# Hank2.net
KiCad netlist of a schematic drawn in EAGLE
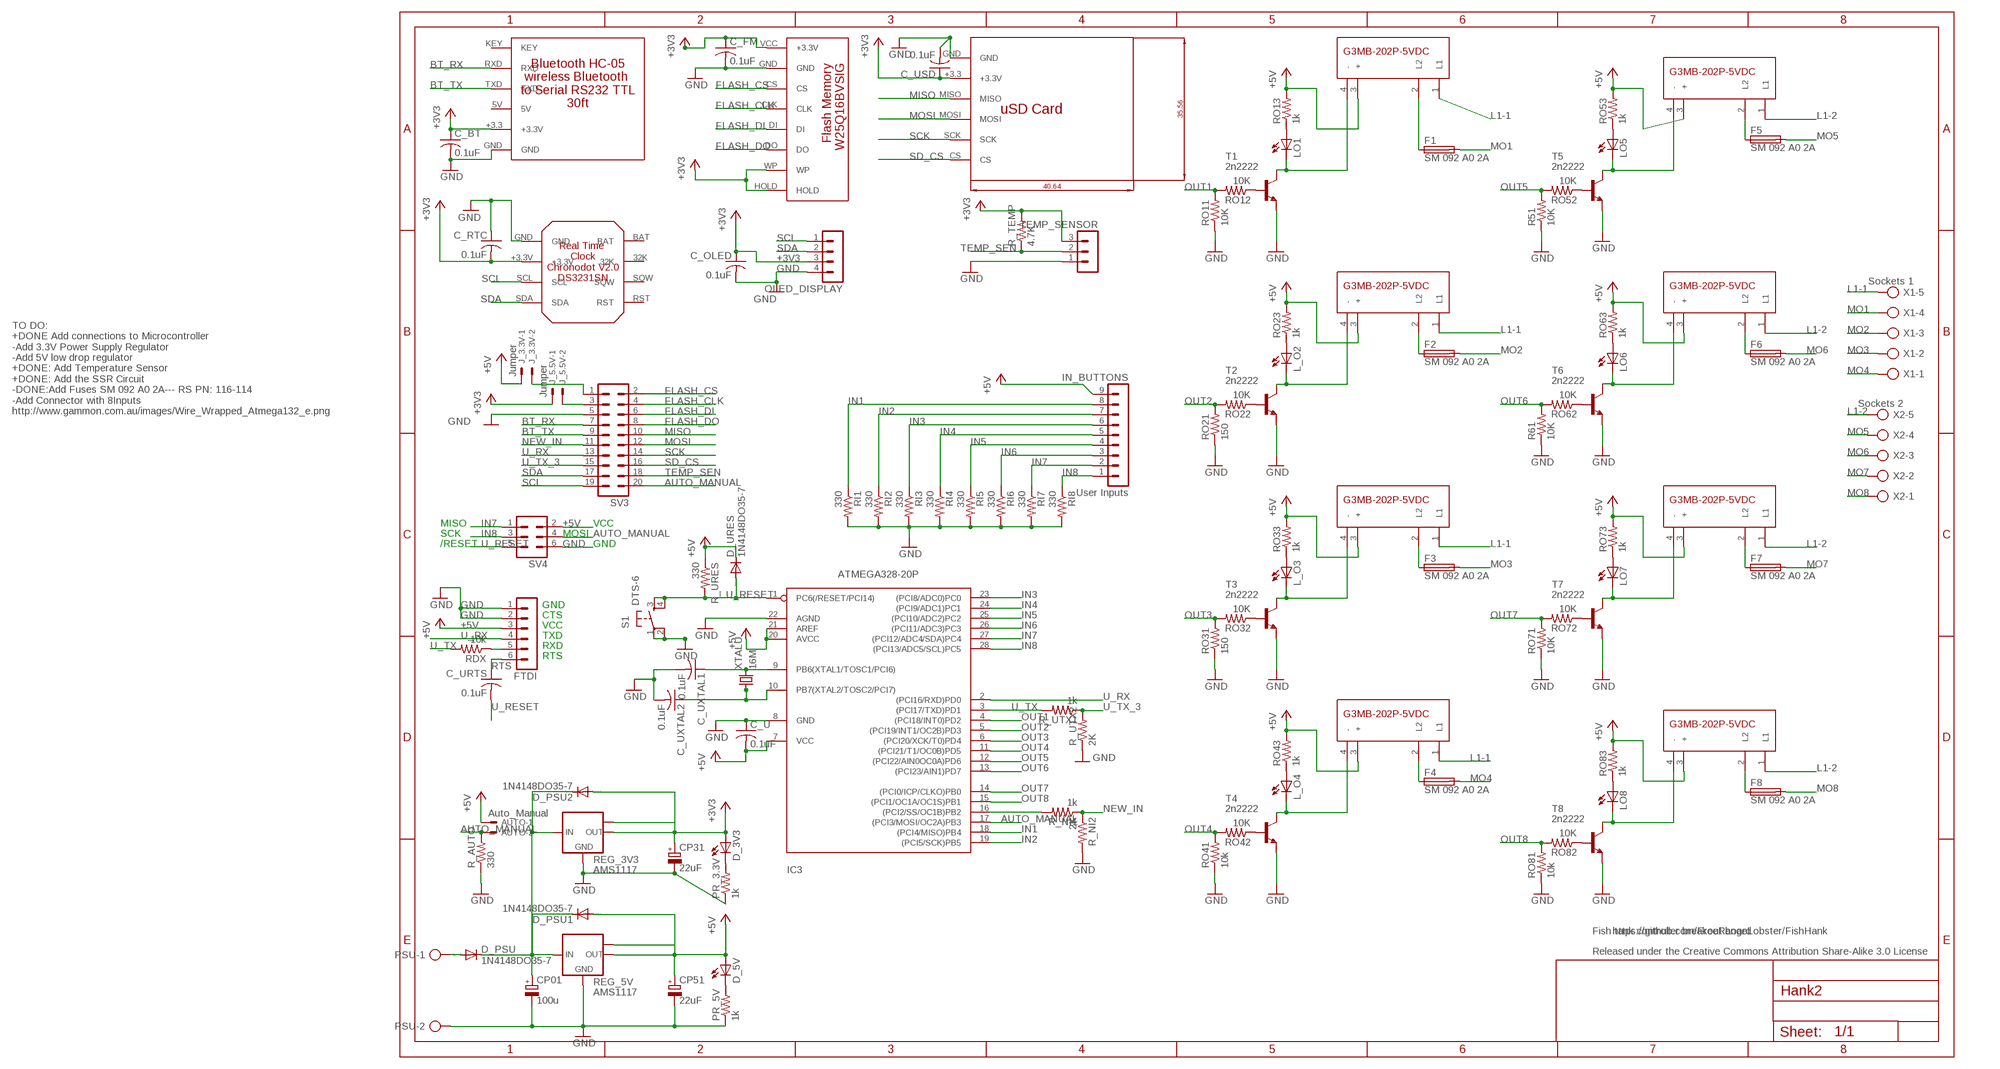
[diagram p0: schematic, sheet 1]

(export (version "E")
  (design (tool "Eeschema 10.0.6"))
  (components
    (comp (ref "AUTO")
      (value "Auto_Manual")
      (footprint "eagle-import:22-23-2021")
      (fields (field (name "MF") "MOLEX") (field (name "MPN") "22-23-2021"))
      (libsource (lib "eagle-import") (part "22-23-2021"))
    )
    (comp (ref "CP01")
      (value "100u")
      (footprint "eagle-import:E2,5-6")
      (libsource (lib "eagle-import") (part "CPOL-EUE2.5-6"))
    )
    (comp (ref "CP31")
      (value "22uF")
      (footprint "eagle-import:E2,5-6")
      (libsource (lib "eagle-import") (part "CPOL-EUE2.5-6"))
    )
    (comp (ref "CP51")
      (value "22uF")
      (footprint "eagle-import:E2,5-6")
      (libsource (lib "eagle-import") (part "CPOL-EUE2.5-6"))
    )
    (comp (ref "C_BT")
      (value "0.1uF")
      (footprint "eagle-import:C025-024X044")
      (libsource (lib "eagle-import") (part "C-US025-024X044"))
    )
    (comp (ref "C_FM")
      (value "0.1uF")
      (footprint "eagle-import:C025-024X044")
      (libsource (lib "eagle-import") (part "C-US025-024X044"))
    )
    (comp (ref "C_OLED")
      (value "0.1uF")
      (footprint "eagle-import:C025-024X044")
      (libsource (lib "eagle-import") (part "C-US025-024X044"))
    )
    (comp (ref "C_RTC")
      (value "0.1uF")
      (footprint "eagle-import:C025-024X044")
      (libsource (lib "eagle-import") (part "C-US025-024X044"))
    )
    (comp (ref "C_U")
      (value "0.1uF")
      (footprint "eagle-import:C025-024X044")
      (libsource (lib "eagle-import") (part "C-US025-024X044"))
    )
    (comp (ref "C_URTS")
      (value "0.1uF")
      (footprint "eagle-import:C025-024X044")
      (libsource (lib "eagle-import") (part "C-US025-024X044"))
    )
    (comp (ref "C_USD")
      (value "0.1uF")
      (footprint "eagle-import:C025-024X044")
      (libsource (lib "eagle-import") (part "C-US025-024X044"))
    )
    (comp (ref "C_UXTAL1")
      (value "0.1uF")
      (footprint "eagle-import:C025-024X044")
      (libsource (lib "eagle-import") (part "C-US025-024X044"))
    )
    (comp (ref "C_UXTAL2")
      (value "0.1uF")
      (footprint "eagle-import:C025-024X044")
      (libsource (lib "eagle-import") (part "C-US025-024X044"))
    )
    (comp (ref "D_3V3")
      (value "LED3MM")
      (footprint "eagle-import:LED3MM")
      (libsource (lib "eagle-import") (part "LED3MM"))
    )
    (comp (ref "D_5V")
      (value "LED3MM")
      (footprint "eagle-import:LED3MM")
      (libsource (lib "eagle-import") (part "LED3MM"))
    )
    (comp (ref "D_PSU")
      (value "1N4148DO35-7")
      (footprint "eagle-import:DO35-7")
      (libsource (lib "eagle-import") (part "1N4148DO35-7"))
    )
    (comp (ref "D_PSU1")
      (value "1N4148DO35-7")
      (footprint "eagle-import:DO35-7")
      (libsource (lib "eagle-import") (part "1N4148DO35-7"))
    )
    (comp (ref "D_PSU2")
      (value "1N4148DO35-7")
      (footprint "eagle-import:DO35-7")
      (libsource (lib "eagle-import") (part "1N4148DO35-7"))
    )
    (comp (ref "D_URES")
      (value "1N4148DO35-7")
      (footprint "eagle-import:DO35-7")
      (libsource (lib "eagle-import") (part "1N4148DO35-7"))
    )
    (comp (ref "F1")
      (value "SM 092 A0 2A")
      (footprint "eagle-import:PICOFUSE")
      (libsource (lib "eagle-import") (part "FUSEPICOFUSE"))
    )
    (comp (ref "F2")
      (value "SM 092 A0 2A")
      (footprint "eagle-import:PICOFUSE")
      (libsource (lib "eagle-import") (part "FUSEPICOFUSE"))
    )
    (comp (ref "F3")
      (value "SM 092 A0 2A")
      (footprint "eagle-import:PICOFUSE")
      (libsource (lib "eagle-import") (part "FUSEPICOFUSE"))
    )
    (comp (ref "F4")
      (value "SM 092 A0 2A")
      (footprint "eagle-import:PICOFUSE")
      (libsource (lib "eagle-import") (part "FUSEPICOFUSE"))
    )
    (comp (ref "F5")
      (value "SM 092 A0 2A")
      (footprint "eagle-import:PICOFUSE")
      (libsource (lib "eagle-import") (part "FUSEPICOFUSE"))
    )
    (comp (ref "F6")
      (value "SM 092 A0 2A")
      (footprint "eagle-import:PICOFUSE")
      (libsource (lib "eagle-import") (part "FUSEPICOFUSE"))
    )
    (comp (ref "F7")
      (value "SM 092 A0 2A")
      (footprint "eagle-import:PICOFUSE")
      (libsource (lib "eagle-import") (part "FUSEPICOFUSE"))
    )
    (comp (ref "F8")
      (value "SM 092 A0 2A")
      (footprint "eagle-import:PICOFUSE")
      (libsource (lib "eagle-import") (part "FUSEPICOFUSE"))
    )
    (comp (ref "FTDI")
      (value "MA06-1")
      (footprint "eagle-import:MA06-1")
      (libsource (lib "eagle-import") (part "MA06-1"))
    )
    (comp (ref "IC3")
      (value "ATMEGA328-20P")
      (footprint "eagle-import:DIL28-3")
      (libsource (lib "eagle-import") (part "ATMEGA328P-20"))
    )
    (comp (ref "IN_BUTTONS")
      (value "User Inputs")
      (footprint "eagle-import:MA09-1")
      (libsource (lib "eagle-import") (part "MA09-1"))
    )
    (comp (ref "J_3.3V")
      (value "Jumper")
      (footprint "eagle-import:22-23-2021")
      (fields (field (name "MF") "MOLEX") (field (name "MPN") "22-23-2021"))
      (libsource (lib "eagle-import") (part "22-23-2021"))
    )
    (comp (ref "J_5.5V")
      (value "Jumper")
      (footprint "eagle-import:22-23-2021")
      (fields (field (name "MF") "MOLEX") (field (name "MPN") "22-23-2021"))
      (libsource (lib "eagle-import") (part "22-23-2021"))
    )
    (comp (ref "LO1")
      (value "LED3MM")
      (footprint "eagle-import:LED3MM")
      (libsource (lib "eagle-import") (part "LED3MM"))
    )
    (comp (ref "LO5")
      (value "LED3MM")
      (footprint "eagle-import:LED3MM")
      (libsource (lib "eagle-import") (part "LED3MM"))
    )
    (comp (ref "LO6")
      (value "LED3MM")
      (footprint "eagle-import:LED3MM")
      (libsource (lib "eagle-import") (part "LED3MM"))
    )
    (comp (ref "LO7")
      (value "LED3MM")
      (footprint "eagle-import:LED3MM")
      (libsource (lib "eagle-import") (part "LED3MM"))
    )
    (comp (ref "LO8")
      (value "LED3MM")
      (footprint "eagle-import:LED3MM")
      (libsource (lib "eagle-import") (part "LED3MM"))
    )
    (comp (ref "L_O2")
      (value "LED3MM")
      (footprint "eagle-import:LED3MM")
      (libsource (lib "eagle-import") (part "LED3MM"))
    )
    (comp (ref "L_O3")
      (value "LED3MM")
      (footprint "eagle-import:LED3MM")
      (libsource (lib "eagle-import") (part "LED3MM"))
    )
    (comp (ref "L_O4")
      (value "LED3MM")
      (footprint "eagle-import:LED3MM")
      (libsource (lib "eagle-import") (part "LED3MM"))
    )
    (comp (ref "OLED_DISPLAY")
      (value "MA04-1")
      (footprint "eagle-import:MA04-1")
      (libsource (lib "eagle-import") (part "MA04-1"))
    )
    (comp (ref "PR_3.3V")
      (value "1k")
      (footprint "eagle-import:0207_10")
      (libsource (lib "eagle-import") (part "R-US_0207/10"))
    )
    (comp (ref "PR_5V")
      (value "1k")
      (footprint "eagle-import:0207_10")
      (libsource (lib "eagle-import") (part "R-US_0207/10"))
    )
    (comp (ref "PSU")
      (value "AK500/2")
      (footprint "eagle-import:AK500_2")
      (libsource (lib "eagle-import") (part "AK500/2"))
    )
    (comp (ref "R51")
      (value "10K")
      (footprint "eagle-import:0207_10")
      (libsource (lib "eagle-import") (part "R-US_0207/10"))
    )
    (comp (ref "R61")
      (value "10K")
      (footprint "eagle-import:0207_10")
      (libsource (lib "eagle-import") (part "R-US_0207/10"))
    )
    (comp (ref "RDX")
      (value "10k")
      (footprint "eagle-import:0207_10")
      (libsource (lib "eagle-import") (part "R-US_0207/10"))
    )
    (comp (ref "REG_3V3")
      (value "AMS1117")
      (footprint "eagle-import:SOT223")
      (libsource (lib "eagle-import") (part "AMS1117"))
    )
    (comp (ref "REG_5V")
      (value "AMS1117")
      (footprint "eagle-import:SOT223")
      (libsource (lib "eagle-import") (part "AMS1117"))
    )
    (comp (ref "RI1")
      (value "330")
      (footprint "eagle-import:0207_10")
      (libsource (lib "eagle-import") (part "R-US_0207/10"))
    )
    (comp (ref "RI2")
      (value "330")
      (footprint "eagle-import:0207_10")
      (libsource (lib "eagle-import") (part "R-US_0207/10"))
    )
    (comp (ref "RI3")
      (value "330")
      (footprint "eagle-import:0207_10")
      (libsource (lib "eagle-import") (part "R-US_0207/10"))
    )
    (comp (ref "RI4")
      (value "330")
      (footprint "eagle-import:0207_10")
      (libsource (lib "eagle-import") (part "R-US_0207/10"))
    )
    (comp (ref "RI5")
      (value "330")
      (footprint "eagle-import:0207_10")
      (libsource (lib "eagle-import") (part "R-US_0207/10"))
    )
    (comp (ref "RI6")
      (value "330")
      (footprint "eagle-import:0207_10")
      (libsource (lib "eagle-import") (part "R-US_0207/10"))
    )
    (comp (ref "RI7")
      (value "330")
      (footprint "eagle-import:0207_10")
      (libsource (lib "eagle-import") (part "R-US_0207/10"))
    )
    (comp (ref "RI8")
      (value "330")
      (footprint "eagle-import:0207_10")
      (libsource (lib "eagle-import") (part "R-US_0207/10"))
    )
    (comp (ref "RO11")
      (value "10K")
      (footprint "eagle-import:0207_10")
      (libsource (lib "eagle-import") (part "R-US_0207/10"))
    )
    (comp (ref "RO12")
      (value "10K")
      (footprint "eagle-import:0207_10")
      (libsource (lib "eagle-import") (part "R-US_0207/10"))
    )
    (comp (ref "RO13")
      (value "1k")
      (footprint "eagle-import:0207_10")
      (libsource (lib "eagle-import") (part "R-US_0207/10"))
    )
    (comp (ref "RO21")
      (value "150")
      (footprint "eagle-import:0207_10")
      (libsource (lib "eagle-import") (part "R-US_0207/10"))
    )
    (comp (ref "RO22")
      (value "10K")
      (footprint "eagle-import:0207_10")
      (libsource (lib "eagle-import") (part "R-US_0207/10"))
    )
    (comp (ref "RO23")
      (value "1k")
      (footprint "eagle-import:0207_10")
      (libsource (lib "eagle-import") (part "R-US_0207/10"))
    )
    (comp (ref "RO31")
      (value "150")
      (footprint "eagle-import:0207_10")
      (libsource (lib "eagle-import") (part "R-US_0207/10"))
    )
    (comp (ref "RO32")
      (value "10K")
      (footprint "eagle-import:0207_10")
      (libsource (lib "eagle-import") (part "R-US_0207/10"))
    )
    (comp (ref "RO33")
      (value "1k")
      (footprint "eagle-import:0207_10")
      (libsource (lib "eagle-import") (part "R-US_0207/10"))
    )
    (comp (ref "RO41")
      (value "10k")
      (footprint "eagle-import:0207_10")
      (libsource (lib "eagle-import") (part "R-US_0207/10"))
    )
    (comp (ref "RO42")
      (value "10K")
      (footprint "eagle-import:0207_10")
      (libsource (lib "eagle-import") (part "R-US_0207/10"))
    )
    (comp (ref "RO43")
      (value "1k")
      (footprint "eagle-import:0207_10")
      (libsource (lib "eagle-import") (part "R-US_0207/10"))
    )
    (comp (ref "RO52")
      (value "10K")
      (footprint "eagle-import:0207_10")
      (libsource (lib "eagle-import") (part "R-US_0207/10"))
    )
    (comp (ref "RO53")
      (value "1k")
      (footprint "eagle-import:0207_10")
      (libsource (lib "eagle-import") (part "R-US_0207/10"))
    )
    (comp (ref "RO62")
      (value "10K")
      (footprint "eagle-import:0207_10")
      (libsource (lib "eagle-import") (part "R-US_0207/10"))
    )
    (comp (ref "RO63")
      (value "1k")
      (footprint "eagle-import:0207_10")
      (libsource (lib "eagle-import") (part "R-US_0207/10"))
    )
    (comp (ref "RO71")
      (value "10K")
      (footprint "eagle-import:0207_10")
      (libsource (lib "eagle-import") (part "R-US_0207/10"))
    )
    (comp (ref "RO72")
      (value "10K")
      (footprint "eagle-import:0207_10")
      (libsource (lib "eagle-import") (part "R-US_0207/10"))
    )
    (comp (ref "RO73")
      (value "1k")
      (footprint "eagle-import:0207_10")
      (libsource (lib "eagle-import") (part "R-US_0207/10"))
    )
    (comp (ref "RO81")
      (value "10k")
      (footprint "eagle-import:0207_10")
      (libsource (lib "eagle-import") (part "R-US_0207/10"))
    )
    (comp (ref "RO82")
      (value "10K")
      (footprint "eagle-import:0207_10")
      (libsource (lib "eagle-import") (part "R-US_0207/10"))
    )
    (comp (ref "RO83")
      (value "1k")
      (footprint "eagle-import:0207_10")
      (libsource (lib "eagle-import") (part "R-US_0207/10"))
    )
    (comp (ref "R_AUTO")
      (value "330")
      (footprint "eagle-import:0207_10")
      (libsource (lib "eagle-import") (part "R-US_0207/10"))
    )
    (comp (ref "R_NI1")
      (value "1k")
      (footprint "eagle-import:0207_10")
      (libsource (lib "eagle-import") (part "R-US_0207/10"))
    )
    (comp (ref "R_NI2")
      (value "2K")
      (footprint "eagle-import:0207_10")
      (libsource (lib "eagle-import") (part "R-US_0207/10"))
    )
    (comp (ref "R_TEMP")
      (value "4.7K")
      (footprint "eagle-import:0207_10")
      (libsource (lib "eagle-import") (part "R-US_0207/10"))
    )
    (comp (ref "R_URES")
      (value "330")
      (footprint "eagle-import:0207_10")
      (libsource (lib "eagle-import") (part "R-US_0207/10"))
    )
    (comp (ref "R_UTX1")
      (value "1k")
      (footprint "eagle-import:0207_10")
      (libsource (lib "eagle-import") (part "R-US_0207/10"))
    )
    (comp (ref "R_UTX2")
      (value "2K")
      (footprint "eagle-import:0207_10")
      (libsource (lib "eagle-import") (part "R-US_0207/10"))
    )
    (comp (ref "S1")
      (value "DTS-6")
      (footprint "eagle-import:DTS-6")
      (libsource (lib "eagle-import") (part "DTS-6"))
    )
    (comp (ref "SSR1")
      (value "SSR")
      (footprint "eagle-import:SSR_FOOTPRINT")
      (libsource (lib "eagle-import") (part "SSR"))
    )
    (comp (ref "SSR2")
      (value "SSR")
      (footprint "eagle-import:SSR_FOOTPRINT")
      (libsource (lib "eagle-import") (part "SSR"))
    )
    (comp (ref "SSR3")
      (value "SSR")
      (footprint "eagle-import:SSR_FOOTPRINT")
      (libsource (lib "eagle-import") (part "SSR"))
    )
    (comp (ref "SSR4")
      (value "SSR")
      (footprint "eagle-import:SSR_FOOTPRINT")
      (libsource (lib "eagle-import") (part "SSR"))
    )
    (comp (ref "SSR5")
      (value "SSR")
      (footprint "eagle-import:SSR_FOOTPRINT")
      (libsource (lib "eagle-import") (part "SSR"))
    )
    (comp (ref "SSR6")
      (value "SSR")
      (footprint "eagle-import:SSR_FOOTPRINT")
      (libsource (lib "eagle-import") (part "SSR"))
    )
    (comp (ref "SSR7")
      (value "SSR")
      (footprint "eagle-import:SSR_FOOTPRINT")
      (libsource (lib "eagle-import") (part "SSR"))
    )
    (comp (ref "SSR8")
      (value "SSR")
      (footprint "eagle-import:SSR_FOOTPRINT")
      (libsource (lib "eagle-import") (part "SSR"))
    )
    (comp (ref "SV3")
      (value "MA10-2")
      (footprint "eagle-import:MA10-2")
      (libsource (lib "eagle-import") (part "MA10-2"))
    )
    (comp (ref "SV4")
      (value "MA03-2")
      (footprint "eagle-import:MA03-2")
      (libsource (lib "eagle-import") (part "MA03-2"))
    )
    (comp (ref "T1")
      (value "2n2222")
      (footprint "eagle-import:TO92-ECB")
      (libsource (lib "eagle-import") (part "2SC458"))
    )
    (comp (ref "T2")
      (value "2n2222")
      (footprint "eagle-import:TO92-ECB")
      (libsource (lib "eagle-import") (part "2SC458"))
    )
    (comp (ref "T3")
      (value "2n2222")
      (footprint "eagle-import:TO92-ECB")
      (libsource (lib "eagle-import") (part "2SC458"))
    )
    (comp (ref "T4")
      (value "2n2222")
      (footprint "eagle-import:TO92-ECB")
      (libsource (lib "eagle-import") (part "2SC458"))
    )
    (comp (ref "T5")
      (value "2n2222")
      (footprint "eagle-import:TO92-ECB")
      (libsource (lib "eagle-import") (part "2SC458"))
    )
    (comp (ref "T6")
      (value "2n2222")
      (footprint "eagle-import:TO92-ECB")
      (libsource (lib "eagle-import") (part "2SC458"))
    )
    (comp (ref "T7")
      (value "2n2222")
      (footprint "eagle-import:TO92-ECB")
      (libsource (lib "eagle-import") (part "2SC458"))
    )
    (comp (ref "T8")
      (value "2n2222")
      (footprint "eagle-import:TO92-ECB")
      (libsource (lib "eagle-import") (part "2SC458"))
    )
    (comp (ref "TEMP_SENSOR")
      (value "MA03-1")
      (footprint "eagle-import:MA03-1")
      (libsource (lib "eagle-import") (part "MA03-1"))
    )
    (comp (ref "U$1")
      (value "FLASH_MEMORY")
      (footprint "eagle-import:FLASHMEMORY_FOOTPRINT")
      (libsource (lib "eagle-import") (part "FLASH_MEMORY"))
    )
    (comp (ref "U$4")
      (value "BLUETOOTH")
      (footprint "eagle-import:BLUETOOTH_FOOTPRINT")
      (libsource (lib "eagle-import") (part "BLUETOOTH"))
    )
    (comp (ref "U$6")
      (value "RTC")
      (footprint "eagle-import:RTC_FOOTPRINT")
      (libsource (lib "eagle-import") (part "RTC"))
    )
    (comp (ref "U$7")
      (value "SD_CARD_READER")
      (footprint "eagle-import:SD_CARD_READER_FOOTPRINT")
      (libsource (lib "eagle-import") (part "SD_CARD_READER"))
    )
    (comp (ref "X1")
      (value "Sockets 1")
      (footprint "eagle-import:AK500_5")
      (libsource (lib "eagle-import") (part "AK500/5"))
    )
    (comp (ref "X2")
      (value "Sockets 2")
      (footprint "eagle-import:AK500_5")
      (libsource (lib "eagle-import") (part "AK500/5"))
    )
    (comp (ref "XTALU")
      (value "16M")
      (footprint "eagle-import:HC49_S")
      (libsource (lib "eagle-import") (part "CRYSTALHC49S"))
    )
  )
  (nets
    (net (code "1") (name "+3V3") (class "Default")
      (node (ref "CP31") (pin "+") (pinfunction "+_+") (pintype "passive"))
      (node (ref "C_BT") (pin "1") (pinfunction "1_1") (pintype "passive"))
      (node (ref "C_FM") (pin "1") (pinfunction "1_1") (pintype "passive"))
      (node (ref "C_OLED") (pin "1") (pinfunction "1_1") (pintype "passive"))
      (node (ref "C_RTC") (pin "2") (pinfunction "2_2") (pintype "passive"))
      (node (ref "C_USD") (pin "1") (pinfunction "1_1") (pintype "passive"))
      (node (ref "D_3V3") (pin "A") (pinfunction "A_A") (pintype "passive"))
      (node (ref "D_PSU2") (pin "A") (pinfunction "A_A") (pintype "passive"))
      (node (ref "J_5.5V") (pin "1") (pinfunction "S_1") (pintype "passive"))
      (node (ref "OLED_DISPLAY") (pin "3") (pinfunction "3_3") (pintype "passive"))
      (node (ref "REG_3V3") (pin "2") (pinfunction "OUT_2") (pintype "passive"))
      (node (ref "REG_3V3") (pin "TAB") (pinfunction "OUT1_TAB") (pintype "passive"))
      (node (ref "R_TEMP") (pin "2") (pinfunction "2_2") (pintype "passive"))
      (node (ref "TEMP_SENSOR") (pin "3") (pinfunction "3_3") (pintype "passive"))
      (node (ref "U$1") (pin "HOLD") (pinfunction "HOLD_HOLD") (pintype "bidirectional"))
      (node (ref "U$1") (pin "VCC") (pinfunction "+3.3V_VCC") (pintype "bidirectional"))
      (node (ref "U$1") (pin "WP") (pinfunction "WP_WP") (pintype "bidirectional"))
      (node (ref "U$4") (pin "+3.3") (pinfunction "+3.3V_+3.3") (pintype "bidirectional"))
      (node (ref "U$6") (pin "+3.3V") (pinfunction "+3.3V_+3.3V") (pintype "bidirectional"))
      (node (ref "U$7") (pin "+3.3") (pinfunction "+3.3V_+3.3") (pintype "bidirectional"))
    )
    (net (code "2") (name "+5V") (class "Default")
      (node (ref "AUTO") (pin "1") (pinfunction "S_1") (pintype "passive"))
      (node (ref "CP51") (pin "+") (pinfunction "+_+") (pintype "passive"))
      (node (ref "C_U") (pin "2") (pinfunction "2_2") (pintype "passive"))
      (node (ref "D_5V") (pin "A") (pinfunction "A_A") (pintype "passive"))
      (node (ref "D_PSU1") (pin "A") (pinfunction "A_A") (pintype "passive"))
      (node (ref "D_URES") (pin "C") (pinfunction "C_C") (pintype "passive"))
      (node (ref "FTDI") (pin "3") (pinfunction "3_3") (pintype "passive"))
      (node (ref "IC3") (pin "20") (pinfunction "AVCC_20") (pintype "bidirectional"))
      (node (ref "IC3") (pin "21") (pinfunction "AREF_21") (pintype "bidirectional"))
      (node (ref "IC3") (pin "7") (pinfunction "VCC_7") (pintype "bidirectional"))
      (node (ref "IN_BUTTONS") (pin "9") (pinfunction "9_9") (pintype "passive"))
      (node (ref "J_3.3V") (pin "1") (pinfunction "S_1") (pintype "passive"))
      (node (ref "REG_5V") (pin "2") (pinfunction "OUT_2") (pintype "passive"))
      (node (ref "REG_5V") (pin "TAB") (pinfunction "OUT1_TAB") (pintype "passive"))
      (node (ref "RO13") (pin "2") (pinfunction "2_2") (pintype "passive"))
      (node (ref "RO23") (pin "2") (pinfunction "2_2") (pintype "passive"))
      (node (ref "RO33") (pin "2") (pinfunction "2_2") (pintype "passive"))
      (node (ref "RO43") (pin "2") (pinfunction "2_2") (pintype "passive"))
      (node (ref "RO53") (pin "2") (pinfunction "2_2") (pintype "passive"))
      (node (ref "RO63") (pin "2") (pinfunction "2_2") (pintype "passive"))
      (node (ref "RO73") (pin "2") (pinfunction "2_2") (pintype "passive"))
      (node (ref "RO83") (pin "2") (pinfunction "2_2") (pintype "passive"))
      (node (ref "R_URES") (pin "1") (pinfunction "1_1") (pintype "passive"))
      (node (ref "SSR1") (pin "3") (pinfunction "+_3") (pintype "bidirectional"))
      (node (ref "SSR2") (pin "3") (pinfunction "+_3") (pintype "bidirectional"))
      (node (ref "SSR3") (pin "3") (pinfunction "+_3") (pintype "bidirectional"))
      (node (ref "SSR4") (pin "3") (pinfunction "+_3") (pintype "bidirectional"))
      (node (ref "SSR5") (pin "3") (pinfunction "+_3") (pintype "bidirectional"))
      (node (ref "SSR6") (pin "3") (pinfunction "+_3") (pintype "bidirectional"))
      (node (ref "SSR7") (pin "3") (pinfunction "+_3") (pintype "bidirectional"))
      (node (ref "SSR8") (pin "3") (pinfunction "+_3") (pintype "bidirectional"))
      (node (ref "SV4") (pin "2") (pinfunction "2_2") (pintype "passive"))
    )
    (net (code "3") (name "/AUTO_MANUAL") (class "Default")
      (node (ref "AUTO") (pin "2") (pinfunction "S_2") (pintype "passive"))
      (node (ref "IC3") (pin "17") (pinfunction "(PCI3/MOSI/OC2A)PB3_17") (pintype "bidirectional"))
      (node (ref "R_AUTO") (pin "2") (pinfunction "2_2") (pintype "passive"))
      (node (ref "SV3") (pin "20") (pinfunction "20_20") (pintype "passive"))
      (node (ref "SV4") (pin "4") (pinfunction "4_4") (pintype "passive"))
    )
    (net (code "4") (name "/BT_RX") (class "Default")
      (node (ref "SV3") (pin "7") (pinfunction "7_7") (pintype "passive"))
      (node (ref "U$4") (pin "RXD") (pinfunction "RXD_RXD") (pintype "bidirectional"))
    )
    (net (code "5") (name "/BT_TX") (class "Default")
      (node (ref "SV3") (pin "9") (pinfunction "9_9") (pintype "passive"))
      (node (ref "U$4") (pin "TXD") (pinfunction "TXD_TXD") (pintype "bidirectional"))
    )
    (net (code "6") (name "/FLASH_CLK") (class "Default")
      (node (ref "SV3") (pin "4") (pinfunction "4_4") (pintype "passive"))
      (node (ref "U$1") (pin "CLK") (pinfunction "CLK_CLK") (pintype "bidirectional"))
    )
    (net (code "7") (name "/FLASH_CS") (class "Default")
      (node (ref "SV3") (pin "2") (pinfunction "2_2") (pintype "passive"))
      (node (ref "U$1") (pin "CS") (pinfunction "CS_CS") (pintype "bidirectional"))
    )
    (net (code "8") (name "/FLASH_DI") (class "Default")
      (node (ref "SV3") (pin "6") (pinfunction "6_6") (pintype "passive"))
      (node (ref "U$1") (pin "DI") (pinfunction "DI_DI") (pintype "bidirectional"))
    )
    (net (code "9") (name "/FLASH_DO") (class "Default")
      (node (ref "SV3") (pin "8") (pinfunction "8_8") (pintype "passive"))
      (node (ref "U$1") (pin "DO") (pinfunction "DO_DO") (pintype "bidirectional"))
    )
    (net (code "10") (name "/IN1") (class "Default")
      (node (ref "IC3") (pin "18") (pinfunction "(PCI4/MISO)PB4_18") (pintype "bidirectional"))
      (node (ref "IN_BUTTONS") (pin "8") (pinfunction "8_8") (pintype "passive"))
      (node (ref "RI1") (pin "1") (pinfunction "1_1") (pintype "passive"))
    )
    (net (code "11") (name "/IN2") (class "Default")
      (node (ref "IC3") (pin "19") (pinfunction "(PCI5/SCK)PB5_19") (pintype "bidirectional"))
      (node (ref "IN_BUTTONS") (pin "7") (pinfunction "7_7") (pintype "passive"))
      (node (ref "RI2") (pin "1") (pinfunction "1_1") (pintype "passive"))
    )
    (net (code "12") (name "/IN3") (class "Default")
      (node (ref "IC3") (pin "23") (pinfunction "(PCI8/ADC0)PC0_23") (pintype "bidirectional"))
      (node (ref "IN_BUTTONS") (pin "6") (pinfunction "6_6") (pintype "passive"))
      (node (ref "RI3") (pin "1") (pinfunction "1_1") (pintype "passive"))
    )
    (net (code "13") (name "/IN4") (class "Default")
      (node (ref "IC3") (pin "24") (pinfunction "(PCI9/ADC1)PC1_24") (pintype "bidirectional"))
      (node (ref "IN_BUTTONS") (pin "5") (pinfunction "5_5") (pintype "passive"))
      (node (ref "RI4") (pin "1") (pinfunction "1_1") (pintype "passive"))
    )
    (net (code "14") (name "/IN5") (class "Default")
      (node (ref "IC3") (pin "25") (pinfunction "(PCI10/ADC2)PC2_25") (pintype "bidirectional"))
      (node (ref "IN_BUTTONS") (pin "4") (pinfunction "4_4") (pintype "passive"))
      (node (ref "RI5") (pin "1") (pinfunction "1_1") (pintype "passive"))
    )
    (net (code "15") (name "/IN6") (class "Default")
      (node (ref "IC3") (pin "26") (pinfunction "(PCI11/ADC3)PC3_26") (pintype "bidirectional"))
      (node (ref "IN_BUTTONS") (pin "3") (pinfunction "3_3") (pintype "passive"))
      (node (ref "RI6") (pin "1") (pinfunction "1_1") (pintype "passive"))
    )
    (net (code "16") (name "/IN7") (class "Default")
      (node (ref "IC3") (pin "27") (pinfunction "(PCI12/ADC4/SDA)PC4_27") (pintype "bidirectional"))
      (node (ref "IN_BUTTONS") (pin "2") (pinfunction "2_2") (pintype "passive"))
      (node (ref "RI7") (pin "1") (pinfunction "1_1") (pintype "passive"))
      (node (ref "SV4") (pin "1") (pinfunction "1_1") (pintype "passive"))
    )
    (net (code "17") (name "/IN8") (class "Default")
      (node (ref "IC3") (pin "28") (pinfunction "(PCI13/ADC5/SCL)PC5_28") (pintype "bidirectional"))
      (node (ref "IN_BUTTONS") (pin "1") (pinfunction "1_1") (pintype "passive"))
      (node (ref "RI8") (pin "1") (pinfunction "1_1") (pintype "passive"))
      (node (ref "SV4") (pin "3") (pinfunction "3_3") (pintype "passive"))
    )
    (net (code "18") (name "/L1-1") (class "Default")
      (node (ref "SSR1") (pin "1") (pinfunction "L1_1") (pintype "bidirectional"))
      (node (ref "SSR2") (pin "1") (pinfunction "L1_1") (pintype "bidirectional"))
      (node (ref "SSR3") (pin "1") (pinfunction "L1_1") (pintype "bidirectional"))
      (node (ref "SSR4") (pin "1") (pinfunction "L1_1") (pintype "bidirectional"))
      (node (ref "X1") (pin "5") (pinfunction "KL_5") (pintype "passive"))
    )
    (net (code "19") (name "/L1-2") (class "Default")
      (node (ref "SSR5") (pin "1") (pinfunction "L1_1") (pintype "bidirectional"))
      (node (ref "SSR6") (pin "1") (pinfunction "L1_1") (pintype "bidirectional"))
      (node (ref "SSR7") (pin "1") (pinfunction "L1_1") (pintype "bidirectional"))
      (node (ref "SSR8") (pin "1") (pinfunction "L1_1") (pintype "bidirectional"))
      (node (ref "X2") (pin "5") (pinfunction "KL_5") (pintype "passive"))
    )
    (net (code "20") (name "/MISO") (class "Default")
      (node (ref "SV3") (pin "10") (pinfunction "10_10") (pintype "passive"))
      (node (ref "U$7") (pin "MISO") (pinfunction "MISO_MISO") (pintype "bidirectional"))
    )
    (net (code "21") (name "/MO1") (class "Default")
      (node (ref "F1") (pin "2") (pinfunction "2_2") (pintype "passive"))
      (node (ref "X1") (pin "4") (pinfunction "KL_4") (pintype "passive"))
    )
    (net (code "22") (name "/MO2") (class "Default")
      (node (ref "F2") (pin "2") (pinfunction "2_2") (pintype "passive"))
      (node (ref "X1") (pin "3") (pinfunction "KL_3") (pintype "passive"))
    )
    (net (code "23") (name "/MO3") (class "Default")
      (node (ref "F3") (pin "2") (pinfunction "2_2") (pintype "passive"))
      (node (ref "X1") (pin "2") (pinfunction "KL_2") (pintype "passive"))
    )
    (net (code "24") (name "/MO4") (class "Default")
      (node (ref "F4") (pin "2") (pinfunction "2_2") (pintype "passive"))
      (node (ref "X1") (pin "1") (pinfunction "KL_1") (pintype "passive"))
    )
    (net (code "25") (name "/MO5") (class "Default")
      (node (ref "F5") (pin "2") (pinfunction "2_2") (pintype "passive"))
      (node (ref "X2") (pin "4") (pinfunction "KL_4") (pintype "passive"))
    )
    (net (code "26") (name "/MO6") (class "Default")
      (node (ref "F6") (pin "2") (pinfunction "2_2") (pintype "passive"))
      (node (ref "X2") (pin "3") (pinfunction "KL_3") (pintype "passive"))
    )
    (net (code "27") (name "/MO7") (class "Default")
      (node (ref "F7") (pin "2") (pinfunction "2_2") (pintype "passive"))
      (node (ref "X2") (pin "2") (pinfunction "KL_2") (pintype "passive"))
    )
    (net (code "28") (name "/MO8") (class "Default")
      (node (ref "F8") (pin "2") (pinfunction "2_2") (pintype "passive"))
      (node (ref "X2") (pin "1") (pinfunction "KL_1") (pintype "passive"))
    )
    (net (code "29") (name "/MOSI") (class "Default")
      (node (ref "SV3") (pin "12") (pinfunction "12_12") (pintype "passive"))
      (node (ref "U$7") (pin "MOSI") (pinfunction "MOSI_MOSI") (pintype "bidirectional"))
    )
    (net (code "30") (name "/NEW_IN") (class "Default")
      (node (ref "R_NI1") (pin "1") (pinfunction "1_1") (pintype "passive"))
      (node (ref "R_NI2") (pin "1") (pinfunction "1_1") (pintype "passive"))
      (node (ref "SV3") (pin "11") (pinfunction "11_11") (pintype "passive"))
    )
    (net (code "31") (name "/OUT1") (class "Default")
      (node (ref "IC3") (pin "4") (pinfunction "(PCI18/INT0)PD2_4") (pintype "bidirectional"))
      (node (ref "RO11") (pin "2") (pinfunction "2_2") (pintype "passive"))
      (node (ref "RO12") (pin "2") (pinfunction "2_2") (pintype "passive"))
    )
    (net (code "32") (name "/OUT2") (class "Default")
      (node (ref "IC3") (pin "5") (pinfunction "(PCI19/INT1/OC2B)PD3_5") (pintype "bidirectional"))
      (node (ref "RO21") (pin "2") (pinfunction "2_2") (pintype "passive"))
      (node (ref "RO22") (pin "2") (pinfunction "2_2") (pintype "passive"))
    )
    (net (code "33") (name "/OUT3") (class "Default")
      (node (ref "IC3") (pin "6") (pinfunction "(PCI20/XCK/T0)PD4_6") (pintype "bidirectional"))
      (node (ref "RO31") (pin "2") (pinfunction "2_2") (pintype "passive"))
      (node (ref "RO32") (pin "2") (pinfunction "2_2") (pintype "passive"))
    )
    (net (code "34") (name "/OUT4") (class "Default")
      (node (ref "IC3") (pin "11") (pinfunction "(PCI21/T1/OC0B)PD5_11") (pintype "bidirectional"))
      (node (ref "RO41") (pin "2") (pinfunction "2_2") (pintype "passive"))
      (node (ref "RO42") (pin "2") (pinfunction "2_2") (pintype "passive"))
    )
    (net (code "35") (name "/OUT5") (class "Default")
      (node (ref "IC3") (pin "12") (pinfunction "(PCI22/AIN0OC0A)PD6_12") (pintype "bidirectional"))
      (node (ref "R51") (pin "2") (pinfunction "2_2") (pintype "passive"))
      (node (ref "RO52") (pin "2") (pinfunction "2_2") (pintype "passive"))
    )
    (net (code "36") (name "/OUT6") (class "Default")
      (node (ref "IC3") (pin "13") (pinfunction "(PCI23/AIN1)PD7_13") (pintype "bidirectional"))
      (node (ref "R61") (pin "2") (pinfunction "2_2") (pintype "passive"))
      (node (ref "RO62") (pin "2") (pinfunction "2_2") (pintype "passive"))
    )
    (net (code "37") (name "/OUT7") (class "Default")
      (node (ref "IC3") (pin "14") (pinfunction "(PCI0/ICP/CLKO)PB0_14") (pintype "bidirectional"))
      (node (ref "RO71") (pin "2") (pinfunction "2_2") (pintype "passive"))
      (node (ref "RO72") (pin "2") (pinfunction "2_2") (pintype "passive"))
    )
    (net (code "38") (name "/OUT8") (class "Default")
      (node (ref "IC3") (pin "15") (pinfunction "(PCI1/OC1A/OC1S)PB1_15") (pintype "bidirectional"))
      (node (ref "RO81") (pin "2") (pinfunction "2_2") (pintype "passive"))
      (node (ref "RO82") (pin "2") (pinfunction "2_2") (pintype "passive"))
    )
    (net (code "39") (name "/RTS") (class "Default")
      (node (ref "C_URTS") (pin "1") (pinfunction "1_1") (pintype "passive"))
      (node (ref "FTDI") (pin "6") (pinfunction "6_6") (pintype "passive"))
    )
    (net (code "40") (name "/SCK") (class "Default")
      (node (ref "SV3") (pin "14") (pinfunction "14_14") (pintype "passive"))
      (node (ref "U$7") (pin "SCK") (pinfunction "SCK_SCK") (pintype "bidirectional"))
    )
    (net (code "41") (name "/SCL") (class "Default")
      (node (ref "OLED_DISPLAY") (pin "1") (pinfunction "1_1") (pintype "passive"))
      (node (ref "SV3") (pin "19") (pinfunction "19_19") (pintype "passive"))
      (node (ref "U$6") (pin "SCL") (pinfunction "SCL_SCL") (pintype "bidirectional"))
    )
    (net (code "42") (name "/SDA") (class "Default")
      (node (ref "OLED_DISPLAY") (pin "2") (pinfunction "2_2") (pintype "passive"))
      (node (ref "SV3") (pin "17") (pinfunction "17_17") (pintype "passive"))
      (node (ref "U$6") (pin "SDA") (pinfunction "SDA_SDA") (pintype "bidirectional"))
    )
    (net (code "43") (name "/SD_CS") (class "Default")
      (node (ref "SV3") (pin "16") (pinfunction "16_16") (pintype "passive"))
      (node (ref "U$7") (pin "CS") (pinfunction "CS_CS") (pintype "bidirectional"))
    )
    (net (code "44") (name "/TEMP_SEN") (class "Default")
      (node (ref "R_TEMP") (pin "1") (pinfunction "1_1") (pintype "passive"))
      (node (ref "SV3") (pin "18") (pinfunction "18_18") (pintype "passive"))
      (node (ref "TEMP_SENSOR") (pin "2") (pinfunction "2_2") (pintype "passive"))
    )
    (net (code "45") (name "/U_RESET") (class "Default")
      (node (ref "C_URTS") (pin "2") (pinfunction "2_2") (pintype "passive"))
      (node (ref "D_URES") (pin "A") (pinfunction "A_A") (pintype "passive"))
      (node (ref "IC3") (pin "1") (pinfunction "PC6(/RESET/PCI14)_1") (pintype "bidirectional"))
      (node (ref "R_URES") (pin "2") (pinfunction "2_2") (pintype "passive"))
      (node (ref "S1") (pin "3") (pinfunction "3_3") (pintype "passive"))
      (node (ref "S1") (pin "4") (pinfunction "4_4") (pintype "passive"))
      (node (ref "SV4") (pin "5") (pinfunction "5_5") (pintype "passive"))
    )
    (net (code "46") (name "/U_RX") (class "Default")
      (node (ref "FTDI") (pin "4") (pinfunction "4_4") (pintype "passive"))
      (node (ref "IC3") (pin "2") (pinfunction "(PCI16/RXD)PD0_2") (pintype "bidirectional"))
      (node (ref "SV3") (pin "13") (pinfunction "13_13") (pintype "passive"))
    )
    (net (code "47") (name "/U_TX") (class "Default")
      (node (ref "IC3") (pin "3") (pinfunction "(PCI17/TXD)PD1_3") (pintype "bidirectional"))
      (node (ref "RDX") (pin "2") (pinfunction "2_2") (pintype "passive"))
      (node (ref "R_UTX1") (pin "2") (pinfunction "2_2") (pintype "passive"))
    )
    (net (code "48") (name "/U_TX_3") (class "Default")
      (node (ref "R_UTX1") (pin "1") (pinfunction "1_1") (pintype "passive"))
      (node (ref "R_UTX2") (pin "2") (pinfunction "2_2") (pintype "passive"))
      (node (ref "SV3") (pin "15") (pinfunction "15_15") (pintype "passive"))
    )
    (net (code "49") (name "GND") (class "Default")
      (node (ref "CP01") (pin "-") (pinfunction "-_-") (pintype "passive"))
      (node (ref "CP31") (pin "-") (pinfunction "-_-") (pintype "passive"))
      (node (ref "CP51") (pin "-") (pinfunction "-_-") (pintype "passive"))
      (node (ref "C_BT") (pin "2") (pinfunction "2_2") (pintype "passive"))
      (node (ref "C_FM") (pin "2") (pinfunction "2_2") (pintype "passive"))
      (node (ref "C_OLED") (pin "2") (pinfunction "2_2") (pintype "passive"))
      (node (ref "C_RTC") (pin "1") (pinfunction "1_1") (pintype "passive"))
      (node (ref "C_U") (pin "1") (pinfunction "1_1") (pintype "passive"))
      (node (ref "C_USD") (pin "2") (pinfunction "2_2") (pintype "passive"))
      (node (ref "C_UXTAL1") (pin "2") (pinfunction "2_2") (pintype "passive"))
      (node (ref "C_UXTAL2") (pin "2") (pinfunction "2_2") (pintype "passive"))
      (node (ref "FTDI") (pin "1") (pinfunction "1_1") (pintype "passive"))
      (node (ref "FTDI") (pin "2") (pinfunction "2_2") (pintype "passive"))
      (node (ref "IC3") (pin "22") (pinfunction "AGND_22") (pintype "bidirectional"))
      (node (ref "IC3") (pin "8") (pinfunction "GND_8") (pintype "bidirectional"))
      (node (ref "OLED_DISPLAY") (pin "4") (pinfunction "4_4") (pintype "passive"))
      (node (ref "PR_3.3V") (pin "1") (pinfunction "1_1") (pintype "passive"))
      (node (ref "PR_5V") (pin "1") (pinfunction "1_1") (pintype "passive"))
      (node (ref "PSU") (pin "2") (pinfunction "KL_2") (pintype "passive"))
      (node (ref "R51") (pin "1") (pinfunction "1_1") (pintype "passive"))
      (node (ref "R61") (pin "1") (pinfunction "1_1") (pintype "passive"))
      (node (ref "REG_3V3") (pin "1") (pinfunction "GND_1") (pintype "input"))
      (node (ref "REG_5V") (pin "1") (pinfunction "GND_1") (pintype "input"))
      (node (ref "RI1") (pin "2") (pinfunction "2_2") (pintype "passive"))
      (node (ref "RI2") (pin "2") (pinfunction "2_2") (pintype "passive"))
      (node (ref "RI3") (pin "2") (pinfunction "2_2") (pintype "passive"))
      (node (ref "RI4") (pin "2") (pinfunction "2_2") (pintype "passive"))
      (node (ref "RI5") (pin "2") (pinfunction "2_2") (pintype "passive"))
      (node (ref "RI6") (pin "2") (pinfunction "2_2") (pintype "passive"))
      (node (ref "RI7") (pin "2") (pinfunction "2_2") (pintype "passive"))
      (node (ref "RI8") (pin "2") (pinfunction "2_2") (pintype "passive"))
      (node (ref "RO11") (pin "1") (pinfunction "1_1") (pintype "passive"))
      (node (ref "RO21") (pin "1") (pinfunction "1_1") (pintype "passive"))
      (node (ref "RO31") (pin "1") (pinfunction "1_1") (pintype "passive"))
      (node (ref "RO41") (pin "1") (pinfunction "1_1") (pintype "passive"))
      (node (ref "RO71") (pin "1") (pinfunction "1_1") (pintype "passive"))
      (node (ref "RO81") (pin "1") (pinfunction "1_1") (pintype "passive"))
      (node (ref "R_AUTO") (pin "1") (pinfunction "1_1") (pintype "passive"))
      (node (ref "R_NI2") (pin "2") (pinfunction "2_2") (pintype "passive"))
      (node (ref "R_UTX2") (pin "1") (pinfunction "1_1") (pintype "passive"))
      (node (ref "S1") (pin "1") (pinfunction "1_1") (pintype "passive"))
      (node (ref "S1") (pin "2") (pinfunction "2_2") (pintype "passive"))
      (node (ref "SV3") (pin "5") (pinfunction "5_5") (pintype "passive"))
      (node (ref "SV4") (pin "6") (pinfunction "6_6") (pintype "passive"))
      (node (ref "T1") (pin "E") (pinfunction "E_E") (pintype "passive"))
      (node (ref "T2") (pin "E") (pinfunction "E_E") (pintype "passive"))
      (node (ref "T3") (pin "E") (pinfunction "E_E") (pintype "passive"))
      (node (ref "T4") (pin "E") (pinfunction "E_E") (pintype "passive"))
      (node (ref "T5") (pin "E") (pinfunction "E_E") (pintype "passive"))
      (node (ref "T6") (pin "E") (pinfunction "E_E") (pintype "passive"))
      (node (ref "T7") (pin "E") (pinfunction "E_E") (pintype "passive"))
      (node (ref "T8") (pin "E") (pinfunction "E_E") (pintype "passive"))
      (node (ref "TEMP_SENSOR") (pin "1") (pinfunction "1_1") (pintype "passive"))
      (node (ref "U$1") (pin "GND") (pinfunction "GND_GND") (pintype "bidirectional"))
      (node (ref "U$4") (pin "GND") (pinfunction "GND_GND") (pintype "bidirectional"))
      (node (ref "U$6") (pin "GND") (pinfunction "GND_GND") (pintype "bidirectional"))
      (node (ref "U$7") (pin "GND") (pinfunction "GND_GND") (pintype "bidirectional"))
    )
    (net (code "50") (name "Net-(D_3V3-C)") (class "Default")
      (node (ref "D_3V3") (pin "K") (pinfunction "C_K") (pintype "passive"))
      (node (ref "PR_3.3V") (pin "2") (pinfunction "2_2") (pintype "passive"))
    )
    (net (code "51") (name "Net-(D_5V-C)") (class "Default")
      (node (ref "D_5V") (pin "K") (pinfunction "C_K") (pintype "passive"))
      (node (ref "PR_5V") (pin "2") (pinfunction "2_2") (pintype "passive"))
    )
    (net (code "52") (name "Net-(FTDI-Pad5)") (class "Default")
      (node (ref "FTDI") (pin "5") (pinfunction "5_5") (pintype "passive"))
      (node (ref "RDX") (pin "1") (pinfunction "1_1") (pintype "passive"))
    )
    (net (code "53") (name "Net-(IC3-(PCI2{slash}SS{slash}OC1B)PB2)") (class "Default")
      (node (ref "IC3") (pin "16") (pinfunction "(PCI2/SS/OC1B)PB2_16") (pintype "bidirectional"))
      (node (ref "R_NI1") (pin "2") (pinfunction "2_2") (pintype "passive"))
    )
    (net (code "54") (name "Net-(IC3-PB6(XTAL1{slash}TOSC1{slash}PCI6))") (class "Default")
      (node (ref "C_UXTAL1") (pin "1") (pinfunction "1_1") (pintype "passive"))
      (node (ref "IC3") (pin "9") (pinfunction "PB6(XTAL1/TOSC1/PCI6)_9") (pintype "bidirectional"))
      (node (ref "XTALU") (pin "2") (pinfunction "2_2") (pintype "passive"))
    )
    (net (code "55") (name "Net-(IC3-PB7(XTAL2{slash}TOSC2{slash}PCI7))") (class "Default")
      (node (ref "C_UXTAL2") (pin "1") (pinfunction "1_1") (pintype "passive"))
      (node (ref "IC3") (pin "10") (pinfunction "PB7(XTAL2/TOSC2/PCI7)_10") (pintype "bidirectional"))
      (node (ref "XTALU") (pin "1") (pinfunction "1_1") (pintype "passive"))
    )
    (net (code "56") (name "Net-(J_3.3VB-S)") (class "Default")
      (node (ref "J_3.3V") (pin "2") (pinfunction "S_2") (pintype "passive"))
      (node (ref "SV3") (pin "1") (pinfunction "1_1") (pintype "passive"))
    )
    (net (code "57") (name "Net-(J_5.5VB-S)") (class "Default")
      (node (ref "J_5.5V") (pin "2") (pinfunction "S_2") (pintype "passive"))
      (node (ref "SV3") (pin "3") (pinfunction "3_3") (pintype "passive"))
    )
    (net (code "58") (name "Net-(LO1-C)") (class "Default")
      (node (ref "LO1") (pin "K") (pinfunction "C_K") (pintype "passive"))
      (node (ref "SSR1") (pin "4") (pinfunction "-_4") (pintype "bidirectional"))
      (node (ref "T1") (pin "C") (pinfunction "C_C") (pintype "passive"))
    )
    (net (code "59") (name "Net-(LO1-PadA)") (class "Default")
      (node (ref "LO1") (pin "A") (pinfunction "A_A") (pintype "passive"))
      (node (ref "RO13") (pin "1") (pinfunction "1_1") (pintype "passive"))
    )
    (net (code "60") (name "Net-(LO5-C)") (class "Default")
      (node (ref "LO5") (pin "K") (pinfunction "C_K") (pintype "passive"))
      (node (ref "SSR5") (pin "4") (pinfunction "-_4") (pintype "bidirectional"))
      (node (ref "T5") (pin "C") (pinfunction "C_C") (pintype "passive"))
    )
    (net (code "61") (name "Net-(LO5-PadA)") (class "Default")
      (node (ref "LO5") (pin "A") (pinfunction "A_A") (pintype "passive"))
      (node (ref "RO53") (pin "1") (pinfunction "1_1") (pintype "passive"))
    )
    (net (code "62") (name "Net-(LO6-C)") (class "Default")
      (node (ref "LO6") (pin "K") (pinfunction "C_K") (pintype "passive"))
      (node (ref "SSR6") (pin "4") (pinfunction "-_4") (pintype "bidirectional"))
      (node (ref "T6") (pin "C") (pinfunction "C_C") (pintype "passive"))
    )
    (net (code "63") (name "Net-(LO6-PadA)") (class "Default")
      (node (ref "LO6") (pin "A") (pinfunction "A_A") (pintype "passive"))
      (node (ref "RO63") (pin "1") (pinfunction "1_1") (pintype "passive"))
    )
    (net (code "64") (name "Net-(LO7-C)") (class "Default")
      (node (ref "LO7") (pin "K") (pinfunction "C_K") (pintype "passive"))
      (node (ref "SSR7") (pin "4") (pinfunction "-_4") (pintype "bidirectional"))
      (node (ref "T7") (pin "C") (pinfunction "C_C") (pintype "passive"))
    )
    (net (code "65") (name "Net-(LO7-PadA)") (class "Default")
      (node (ref "LO7") (pin "A") (pinfunction "A_A") (pintype "passive"))
      (node (ref "RO73") (pin "1") (pinfunction "1_1") (pintype "passive"))
    )
    (net (code "66") (name "Net-(LO8-C)") (class "Default")
      (node (ref "LO8") (pin "K") (pinfunction "C_K") (pintype "passive"))
      (node (ref "SSR8") (pin "4") (pinfunction "-_4") (pintype "bidirectional"))
      (node (ref "T8") (pin "C") (pinfunction "C_C") (pintype "passive"))
    )
    (net (code "67") (name "Net-(LO8-PadA)") (class "Default")
      (node (ref "LO8") (pin "A") (pinfunction "A_A") (pintype "passive"))
      (node (ref "RO83") (pin "1") (pinfunction "1_1") (pintype "passive"))
    )
    (net (code "68") (name "Net-(L_O2-C)") (class "Default")
      (node (ref "L_O2") (pin "K") (pinfunction "C_K") (pintype "passive"))
      (node (ref "SSR2") (pin "4") (pinfunction "-_4") (pintype "bidirectional"))
      (node (ref "T2") (pin "C") (pinfunction "C_C") (pintype "passive"))
    )
    (net (code "69") (name "Net-(L_O2-PadA)") (class "Default")
      (node (ref "L_O2") (pin "A") (pinfunction "A_A") (pintype "passive"))
      (node (ref "RO23") (pin "1") (pinfunction "1_1") (pintype "passive"))
    )
    (net (code "70") (name "Net-(L_O3-C)") (class "Default")
      (node (ref "L_O3") (pin "K") (pinfunction "C_K") (pintype "passive"))
      (node (ref "SSR3") (pin "4") (pinfunction "-_4") (pintype "bidirectional"))
      (node (ref "T3") (pin "C") (pinfunction "C_C") (pintype "passive"))
    )
    (net (code "71") (name "Net-(L_O3-PadA)") (class "Default")
      (node (ref "L_O3") (pin "A") (pinfunction "A_A") (pintype "passive"))
      (node (ref "RO33") (pin "1") (pinfunction "1_1") (pintype "passive"))
    )
    (net (code "72") (name "Net-(L_O4-C)") (class "Default")
      (node (ref "L_O4") (pin "K") (pinfunction "C_K") (pintype "passive"))
      (node (ref "SSR4") (pin "4") (pinfunction "-_4") (pintype "bidirectional"))
      (node (ref "T4") (pin "C") (pinfunction "C_C") (pintype "passive"))
    )
    (net (code "73") (name "Net-(L_O4-PadA)") (class "Default")
      (node (ref "L_O4") (pin "A") (pinfunction "A_A") (pintype "passive"))
      (node (ref "RO43") (pin "1") (pinfunction "1_1") (pintype "passive"))
    )
    (net (code "74") (name "Net-(PSUA-KL)") (class "Default")
      (node (ref "D_PSU") (pin "A") (pinfunction "A_A") (pintype "passive"))
      (node (ref "PSU") (pin "1") (pinfunction "KL_1") (pintype "passive"))
    )
    (net (code "75") (name "Net-(REG_3V3-IN)") (class "Default")
      (node (ref "CP01") (pin "+") (pinfunction "+_+") (pintype "passive"))
      (node (ref "D_PSU") (pin "C") (pinfunction "C_C") (pintype "passive"))
      (node (ref "D_PSU1") (pin "C") (pinfunction "C_C") (pintype "passive"))
      (node (ref "D_PSU2") (pin "C") (pinfunction "C_C") (pintype "passive"))
      (node (ref "REG_3V3") (pin "3") (pinfunction "IN_3") (pintype "input"))
      (node (ref "REG_5V") (pin "3") (pinfunction "IN_3") (pintype "input"))
    )
    (net (code "76") (name "Net-(RO12-Pad1)") (class "Default")
      (node (ref "RO12") (pin "1") (pinfunction "1_1") (pintype "passive"))
      (node (ref "T1") (pin "B") (pinfunction "B_B") (pintype "passive"))
    )
    (net (code "77") (name "Net-(RO22-Pad1)") (class "Default")
      (node (ref "RO22") (pin "1") (pinfunction "1_1") (pintype "passive"))
      (node (ref "T2") (pin "B") (pinfunction "B_B") (pintype "passive"))
    )
    (net (code "78") (name "Net-(RO32-Pad1)") (class "Default")
      (node (ref "RO32") (pin "1") (pinfunction "1_1") (pintype "passive"))
      (node (ref "T3") (pin "B") (pinfunction "B_B") (pintype "passive"))
    )
    (net (code "79") (name "Net-(RO42-Pad1)") (class "Default")
      (node (ref "RO42") (pin "1") (pinfunction "1_1") (pintype "passive"))
      (node (ref "T4") (pin "B") (pinfunction "B_B") (pintype "passive"))
    )
    (net (code "80") (name "Net-(RO52-Pad1)") (class "Default")
      (node (ref "RO52") (pin "1") (pinfunction "1_1") (pintype "passive"))
      (node (ref "T5") (pin "B") (pinfunction "B_B") (pintype "passive"))
    )
    (net (code "81") (name "Net-(RO62-Pad1)") (class "Default")
      (node (ref "RO62") (pin "1") (pinfunction "1_1") (pintype "passive"))
      (node (ref "T6") (pin "B") (pinfunction "B_B") (pintype "passive"))
    )
    (net (code "82") (name "Net-(RO72-Pad1)") (class "Default")
      (node (ref "RO72") (pin "1") (pinfunction "1_1") (pintype "passive"))
      (node (ref "T7") (pin "B") (pinfunction "B_B") (pintype "passive"))
    )
    (net (code "83") (name "Net-(RO82-Pad1)") (class "Default")
      (node (ref "RO82") (pin "1") (pinfunction "1_1") (pintype "passive"))
      (node (ref "T8") (pin "B") (pinfunction "B_B") (pintype "passive"))
    )
    (net (code "84") (name "Net-(SSR1-L2)") (class "Default")
      (node (ref "F1") (pin "1") (pinfunction "1_1") (pintype "passive"))
      (node (ref "SSR1") (pin "2") (pinfunction "L2_2") (pintype "bidirectional"))
    )
    (net (code "85") (name "Net-(SSR2-L2)") (class "Default")
      (node (ref "F2") (pin "1") (pinfunction "1_1") (pintype "passive"))
      (node (ref "SSR2") (pin "2") (pinfunction "L2_2") (pintype "bidirectional"))
    )
    (net (code "86") (name "Net-(SSR3-L2)") (class "Default")
      (node (ref "F3") (pin "1") (pinfunction "1_1") (pintype "passive"))
      (node (ref "SSR3") (pin "2") (pinfunction "L2_2") (pintype "bidirectional"))
    )
    (net (code "87") (name "Net-(SSR4-L2)") (class "Default")
      (node (ref "F4") (pin "1") (pinfunction "1_1") (pintype "passive"))
      (node (ref "SSR4") (pin "2") (pinfunction "L2_2") (pintype "bidirectional"))
    )
    (net (code "88") (name "Net-(SSR5-L2)") (class "Default")
      (node (ref "F5") (pin "1") (pinfunction "1_1") (pintype "passive"))
      (node (ref "SSR5") (pin "2") (pinfunction "L2_2") (pintype "bidirectional"))
    )
    (net (code "89") (name "Net-(SSR6-L2)") (class "Default")
      (node (ref "F6") (pin "1") (pinfunction "1_1") (pintype "passive"))
      (node (ref "SSR6") (pin "2") (pinfunction "L2_2") (pintype "bidirectional"))
    )
    (net (code "90") (name "Net-(SSR7-L2)") (class "Default")
      (node (ref "F7") (pin "1") (pinfunction "1_1") (pintype "passive"))
      (node (ref "SSR7") (pin "2") (pinfunction "L2_2") (pintype "bidirectional"))
    )
    (net (code "91") (name "Net-(SSR8-L2)") (class "Default")
      (node (ref "F8") (pin "1") (pinfunction "1_1") (pintype "passive"))
      (node (ref "SSR8") (pin "2") (pinfunction "L2_2") (pintype "bidirectional"))
    )
    (net (code "92") (name "unconnected-(U$4-Pad5V)") (class "Default")
      (node (ref "U$4") (pin "5V") (pinfunction "5V_5V") (pintype "bidirectional"))
    )
    (net (code "93") (name "unconnected-(U$4-PadKEY)") (class "Default")
      (node (ref "U$4") (pin "KEY") (pinfunction "KEY_KEY") (pintype "bidirectional"))
    )
    (net (code "94") (name "unconnected-(U$6-Pad32K)") (class "Default")
      (node (ref "U$6") (pin "32K") (pinfunction "32K_32K") (pintype "bidirectional"))
    )
    (net (code "95") (name "unconnected-(U$6-PadBAT)") (class "Default")
      (node (ref "U$6") (pin "BAT") (pinfunction "BAT_BAT") (pintype "bidirectional"))
    )
    (net (code "96") (name "unconnected-(U$6-PadRST)") (class "Default")
      (node (ref "U$6") (pin "RST") (pinfunction "RST_RST") (pintype "bidirectional"))
    )
    (net (code "97") (name "unconnected-(U$6-PadSQW)") (class "Default")
      (node (ref "U$6") (pin "SQW") (pinfunction "SQW_SQW") (pintype "bidirectional"))
    )
  )
)
